# BeoModern_display.net
KiCad netlist of a schematic drawn in EAGLE
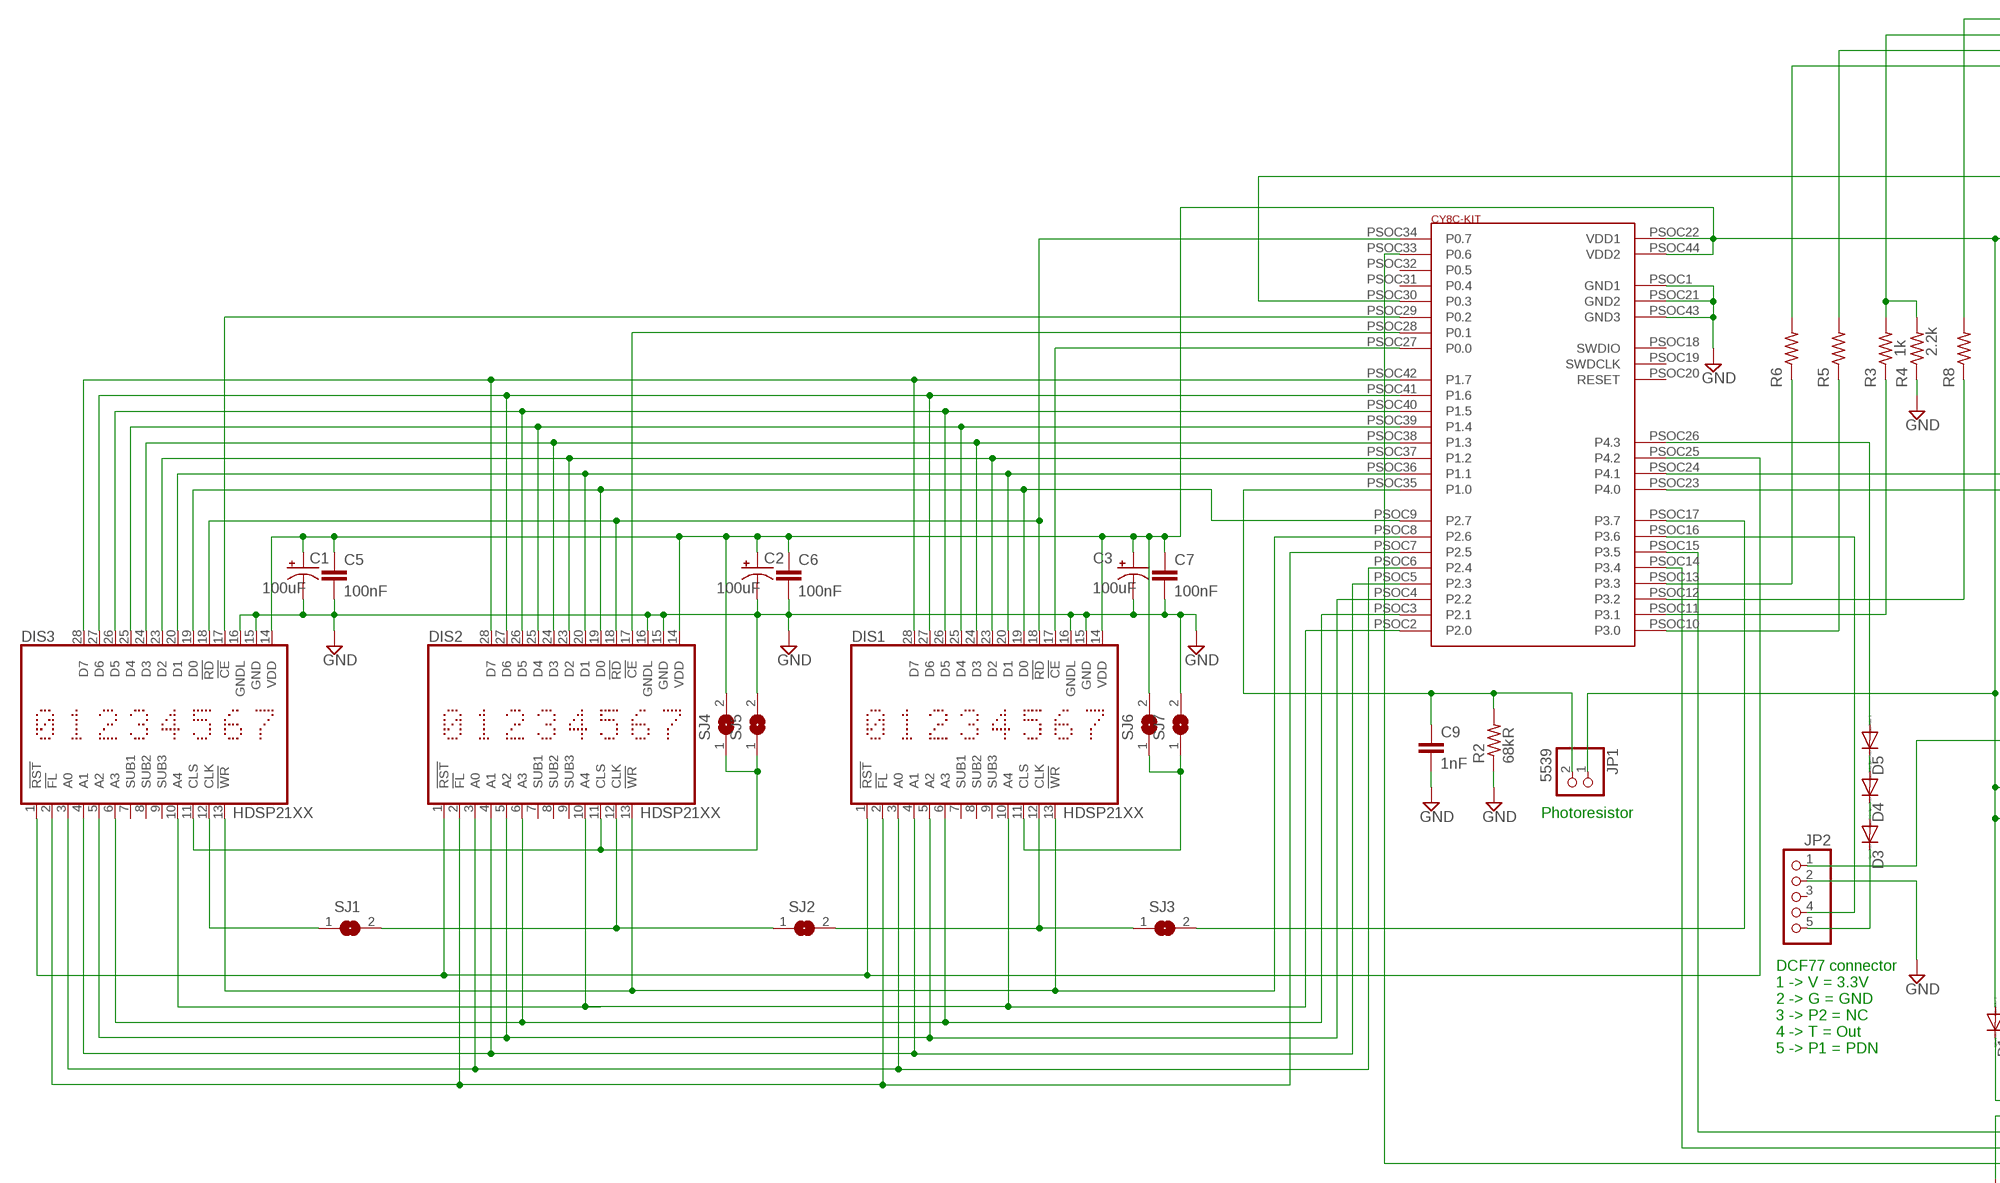
[diagram p0: schematic, sheet 1, part 1 of 2]
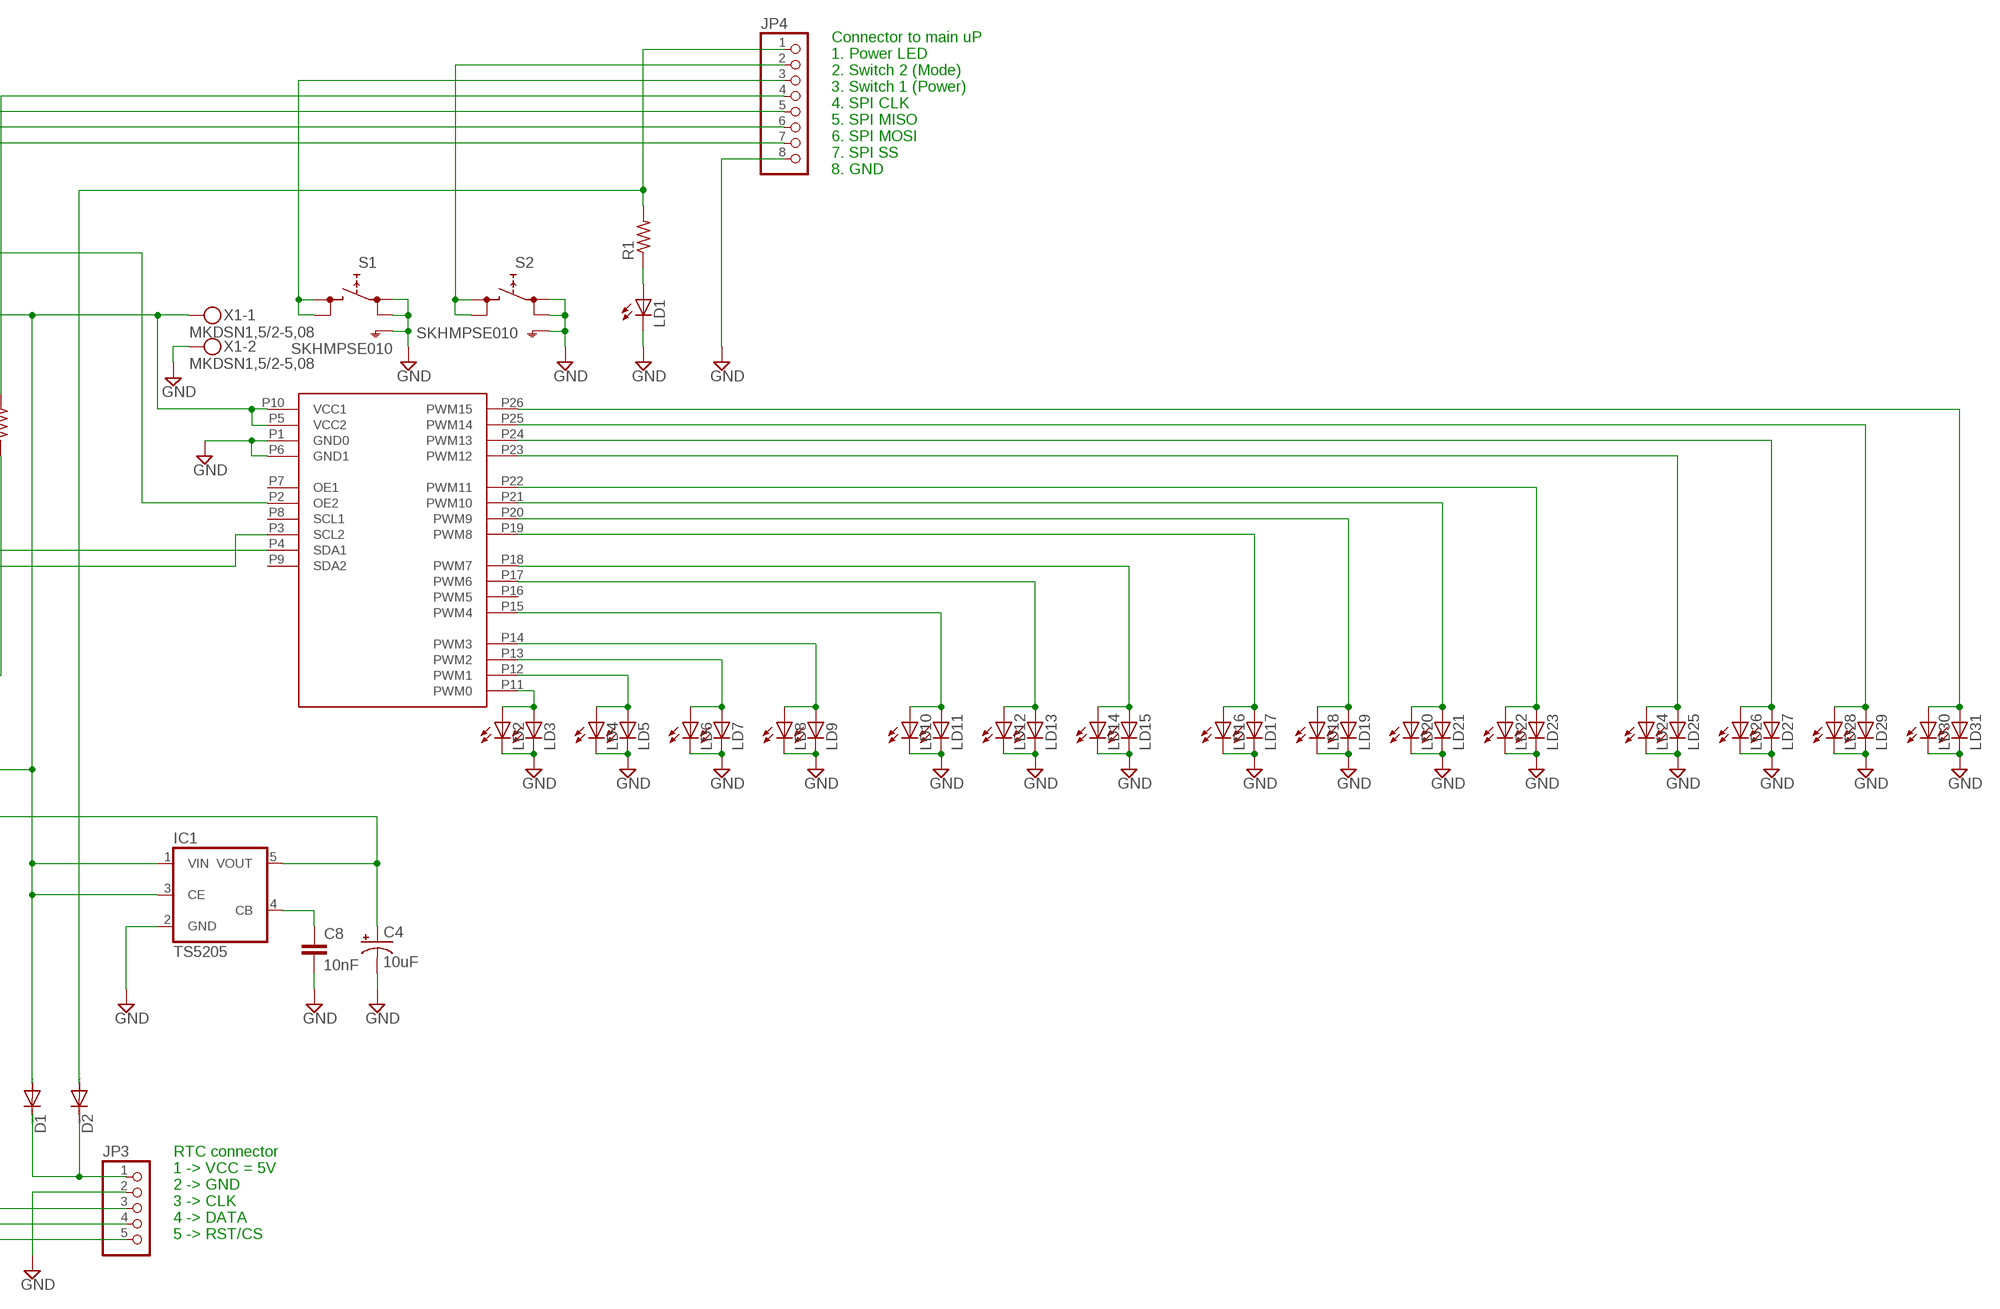
[diagram p1: schematic, sheet 1, part 2 of 2]

(export (version "E")
  (design (tool "Eeschema 10.0.6"))
  (components
    (comp (ref "C1")
      (value "100uF")
      (footprint "eagle-import:E15-5")
      (libsource (lib "eagle-import") (part "CPOL-USE15-5AXIAL"))
    )
    (comp (ref "C2")
      (value "100uF")
      (footprint "eagle-import:E15-5")
      (libsource (lib "eagle-import") (part "CPOL-USE15-5AXIAL"))
    )
    (comp (ref "C3")
      (value "100uF")
      (footprint "eagle-import:E15-5")
      (libsource (lib "eagle-import") (part "CPOL-USE15-5AXIAL"))
    )
    (comp (ref "C4")
      (value "10uF")
      (footprint "eagle-import:E2,5-5")
      (libsource (lib "eagle-import") (part "CPOL-USE2.5-5"))
    )
    (comp (ref "C5")
      (value "100nF")
      (footprint "eagle-import:C15B5")
      (libsource (lib "eagle-import") (part "C15/5"))
    )
    (comp (ref "C6")
      (value "100nF")
      (footprint "eagle-import:C15B5")
      (libsource (lib "eagle-import") (part "C15/5"))
    )
    (comp (ref "C7")
      (value "100nF")
      (footprint "eagle-import:C15B5")
      (libsource (lib "eagle-import") (part "C15/5"))
    )
    (comp (ref "C8")
      (value "10nF")
      (footprint "eagle-import:C2.5-2")
      (libsource (lib "eagle-import") (part "C2.5/2"))
    )
    (comp (ref "C9")
      (value "1nF")
      (footprint "eagle-import:C2.5-2")
      (libsource (lib "eagle-import") (part "C2.5/2"))
    )
    (comp (ref "D1")
      (value "DIODE-SOD80C")
      (footprint "eagle-import:SOD80C")
      (libsource (lib "eagle-import") (part "DIODE-SOD80C"))
    )
    (comp (ref "D2")
      (value "DIODE-SOD80C")
      (footprint "eagle-import:SOD80C")
      (libsource (lib "eagle-import") (part "DIODE-SOD80C"))
    )
    (comp (ref "D3")
      (value "DIODE-SOD80C")
      (footprint "eagle-import:SOD80C")
      (libsource (lib "eagle-import") (part "DIODE-SOD80C"))
    )
    (comp (ref "D4")
      (value "DIODE-SOD80C")
      (footprint "eagle-import:SOD80C")
      (libsource (lib "eagle-import") (part "DIODE-SOD80C"))
    )
    (comp (ref "D5")
      (value "DIODE-SOD80C")
      (footprint "eagle-import:SOD80C")
      (libsource (lib "eagle-import") (part "DIODE-SOD80C"))
    )
    (comp (ref "DIS1")
      (value "HDSP21XX")
      (footprint "eagle-import:HDSP21XX")
      (fields (field (name "MF") "AGILENT TECHNOLOGIES") (field (name "MPN") "HDSP-2179"))
      (libsource (lib "eagle-import") (part "HDSP21XX"))
    )
    (comp (ref "DIS2")
      (value "HDSP21XX")
      (footprint "eagle-import:HDSP21XX")
      (fields (field (name "MF") "AGILENT TECHNOLOGIES") (field (name "MPN") "HDSP-2179"))
      (libsource (lib "eagle-import") (part "HDSP21XX"))
    )
    (comp (ref "DIS3")
      (value "HDSP21XX")
      (footprint "eagle-import:HDSP21XX")
      (fields (field (name "MF") "AGILENT TECHNOLOGIES") (field (name "MPN") "HDSP-2179"))
      (libsource (lib "eagle-import") (part "HDSP21XX"))
    )
    (comp (ref "IC1")
      (value "TS5205")
      (footprint "eagle-import:SOT25")
      (libsource (lib "eagle-import") (part "TS5205"))
    )
    (comp (ref "JP1")
      (value "5539")
      (footprint "eagle-import:1X02")
      (libsource (lib "eagle-import") (part "PINHD-1X2"))
    )
    (comp (ref "JP2")
      (value "PINHD-1X5")
      (footprint "eagle-import:1X05")
      (libsource (lib "eagle-import") (part "PINHD-1X5"))
    )
    (comp (ref "JP3")
      (value "PINHD-1X5")
      (footprint "eagle-import:1X05")
      (libsource (lib "eagle-import") (part "PINHD-1X5"))
    )
    (comp (ref "JP4")
      (value "PINHD-1X8")
      (footprint "eagle-import:1X08")
      (libsource (lib "eagle-import") (part "PINHD-1X8"))
    )
    (comp (ref "LD1")
      (value "TLLR4400")
      (footprint "eagle-import:LED3MM")
      (fields (field (name "MF") "VISHAY SEMICONDUCTOR"))
      (libsource (lib "eagle-import") (part "TLLR4400"))
    )
    (comp (ref "LD2")
      (value "TLLR4400")
      (footprint "eagle-import:LED3MM")
      (fields (field (name "MF") "VISHAY SEMICONDUCTOR"))
      (libsource (lib "eagle-import") (part "TLLR4400"))
    )
    (comp (ref "LD3")
      (value "TLLR4400")
      (footprint "eagle-import:LED3MM")
      (fields (field (name "MF") "VISHAY SEMICONDUCTOR"))
      (libsource (lib "eagle-import") (part "TLLR4400"))
    )
    (comp (ref "LD4")
      (value "TLLR4400")
      (footprint "eagle-import:LED3MM")
      (fields (field (name "MF") "VISHAY SEMICONDUCTOR"))
      (libsource (lib "eagle-import") (part "TLLR4400"))
    )
    (comp (ref "LD5")
      (value "TLLR4400")
      (footprint "eagle-import:LED3MM")
      (fields (field (name "MF") "VISHAY SEMICONDUCTOR"))
      (libsource (lib "eagle-import") (part "TLLR4400"))
    )
    (comp (ref "LD6")
      (value "TLLR4400")
      (footprint "eagle-import:LED3MM")
      (fields (field (name "MF") "VISHAY SEMICONDUCTOR"))
      (libsource (lib "eagle-import") (part "TLLR4400"))
    )
    (comp (ref "LD7")
      (value "TLLR4400")
      (footprint "eagle-import:LED3MM")
      (fields (field (name "MF") "VISHAY SEMICONDUCTOR"))
      (libsource (lib "eagle-import") (part "TLLR4400"))
    )
    (comp (ref "LD8")
      (value "TLLR4400")
      (footprint "eagle-import:LED3MM")
      (fields (field (name "MF") "VISHAY SEMICONDUCTOR"))
      (libsource (lib "eagle-import") (part "TLLR4400"))
    )
    (comp (ref "LD9")
      (value "TLLR4400")
      (footprint "eagle-import:LED3MM")
      (fields (field (name "MF") "VISHAY SEMICONDUCTOR"))
      (libsource (lib "eagle-import") (part "TLLR4400"))
    )
    (comp (ref "LD10")
      (value "TLLR4400")
      (footprint "eagle-import:LED3MM")
      (fields (field (name "MF") "VISHAY SEMICONDUCTOR"))
      (libsource (lib "eagle-import") (part "TLLR4400"))
    )
    (comp (ref "LD11")
      (value "TLLR4400")
      (footprint "eagle-import:LED3MM")
      (fields (field (name "MF") "VISHAY SEMICONDUCTOR"))
      (libsource (lib "eagle-import") (part "TLLR4400"))
    )
    (comp (ref "LD12")
      (value "TLLR4400")
      (footprint "eagle-import:LED3MM")
      (fields (field (name "MF") "VISHAY SEMICONDUCTOR"))
      (libsource (lib "eagle-import") (part "TLLR4400"))
    )
    (comp (ref "LD13")
      (value "TLLR4400")
      (footprint "eagle-import:LED3MM")
      (fields (field (name "MF") "VISHAY SEMICONDUCTOR"))
      (libsource (lib "eagle-import") (part "TLLR4400"))
    )
    (comp (ref "LD14")
      (value "TLLR4400")
      (footprint "eagle-import:LED3MM")
      (fields (field (name "MF") "VISHAY SEMICONDUCTOR"))
      (libsource (lib "eagle-import") (part "TLLR4400"))
    )
    (comp (ref "LD15")
      (value "TLLR4400")
      (footprint "eagle-import:LED3MM")
      (fields (field (name "MF") "VISHAY SEMICONDUCTOR"))
      (libsource (lib "eagle-import") (part "TLLR4400"))
    )
    (comp (ref "LD16")
      (value "TLLR4400")
      (footprint "eagle-import:LED3MM")
      (fields (field (name "MF") "VISHAY SEMICONDUCTOR"))
      (libsource (lib "eagle-import") (part "TLLR4400"))
    )
    (comp (ref "LD17")
      (value "TLLR4400")
      (footprint "eagle-import:LED3MM")
      (fields (field (name "MF") "VISHAY SEMICONDUCTOR"))
      (libsource (lib "eagle-import") (part "TLLR4400"))
    )
    (comp (ref "LD18")
      (value "TLLR4400")
      (footprint "eagle-import:LED3MM")
      (fields (field (name "MF") "VISHAY SEMICONDUCTOR"))
      (libsource (lib "eagle-import") (part "TLLR4400"))
    )
    (comp (ref "LD19")
      (value "TLLR4400")
      (footprint "eagle-import:LED3MM")
      (fields (field (name "MF") "VISHAY SEMICONDUCTOR"))
      (libsource (lib "eagle-import") (part "TLLR4400"))
    )
    (comp (ref "LD20")
      (value "TLLR4400")
      (footprint "eagle-import:LED3MM")
      (fields (field (name "MF") "VISHAY SEMICONDUCTOR"))
      (libsource (lib "eagle-import") (part "TLLR4400"))
    )
    (comp (ref "LD21")
      (value "TLLR4400")
      (footprint "eagle-import:LED3MM")
      (fields (field (name "MF") "VISHAY SEMICONDUCTOR"))
      (libsource (lib "eagle-import") (part "TLLR4400"))
    )
    (comp (ref "LD22")
      (value "TLLR4400")
      (footprint "eagle-import:LED3MM")
      (fields (field (name "MF") "VISHAY SEMICONDUCTOR"))
      (libsource (lib "eagle-import") (part "TLLR4400"))
    )
    (comp (ref "LD23")
      (value "TLLR4400")
      (footprint "eagle-import:LED3MM")
      (fields (field (name "MF") "VISHAY SEMICONDUCTOR"))
      (libsource (lib "eagle-import") (part "TLLR4400"))
    )
    (comp (ref "LD24")
      (value "TLLR4400")
      (footprint "eagle-import:LED3MM")
      (fields (field (name "MF") "VISHAY SEMICONDUCTOR"))
      (libsource (lib "eagle-import") (part "TLLR4400"))
    )
    (comp (ref "LD25")
      (value "TLLR4400")
      (footprint "eagle-import:LED3MM")
      (fields (field (name "MF") "VISHAY SEMICONDUCTOR"))
      (libsource (lib "eagle-import") (part "TLLR4400"))
    )
    (comp (ref "LD26")
      (value "TLLR4400")
      (footprint "eagle-import:LED3MM")
      (fields (field (name "MF") "VISHAY SEMICONDUCTOR"))
      (libsource (lib "eagle-import") (part "TLLR4400"))
    )
    (comp (ref "LD27")
      (value "TLLR4400")
      (footprint "eagle-import:LED3MM")
      (fields (field (name "MF") "VISHAY SEMICONDUCTOR"))
      (libsource (lib "eagle-import") (part "TLLR4400"))
    )
    (comp (ref "LD28")
      (value "TLLR4400")
      (footprint "eagle-import:LED3MM")
      (fields (field (name "MF") "VISHAY SEMICONDUCTOR"))
      (libsource (lib "eagle-import") (part "TLLR4400"))
    )
    (comp (ref "LD29")
      (value "TLLR4400")
      (footprint "eagle-import:LED3MM")
      (fields (field (name "MF") "VISHAY SEMICONDUCTOR"))
      (libsource (lib "eagle-import") (part "TLLR4400"))
    )
    (comp (ref "LD30")
      (value "TLLR4400")
      (footprint "eagle-import:LED3MM")
      (fields (field (name "MF") "VISHAY SEMICONDUCTOR"))
      (libsource (lib "eagle-import") (part "TLLR4400"))
    )
    (comp (ref "LD31")
      (value "TLLR4400")
      (footprint "eagle-import:LED3MM")
      (fields (field (name "MF") "VISHAY SEMICONDUCTOR"))
      (libsource (lib "eagle-import") (part "TLLR4400"))
    )
    (comp (ref "R1")
      (value "R-US_0207/10")
      (footprint "eagle-import:0207_10")
      (libsource (lib "eagle-import") (part "R-US_0207/10"))
    )
    (comp (ref "R2")
      (value "68kR")
      (footprint "eagle-import:0207_10")
      (libsource (lib "eagle-import") (part "R-US_0207/10"))
    )
    (comp (ref "R3")
      (value "1k")
      (footprint "eagle-import:0207_10")
      (libsource (lib "eagle-import") (part "R-US_0207/10"))
    )
    (comp (ref "R4")
      (value "2.2k")
      (footprint "eagle-import:0207_10")
      (libsource (lib "eagle-import") (part "R-US_0207/10"))
    )
    (comp (ref "R5")
      (value "R-US_0207/10")
      (footprint "eagle-import:0207_10")
      (libsource (lib "eagle-import") (part "R-US_0207/10"))
    )
    (comp (ref "R6")
      (value "R-US_0207/10")
      (footprint "eagle-import:0207_10")
      (libsource (lib "eagle-import") (part "R-US_0207/10"))
    )
    (comp (ref "R8")
      (value "R-US_0207/10")
      (footprint "eagle-import:0207_10")
      (libsource (lib "eagle-import") (part "R-US_0207/10"))
    )
    (comp (ref "S1")
      (value "SKHMPSE010")
      (footprint "eagle-import:SKHMPXE010")
      (libsource (lib "eagle-import") (part "SKHMPE010S"))
    )
    (comp (ref "S2")
      (value "SKHMPSE010")
      (footprint "eagle-import:SKHMPXE010")
      (libsource (lib "eagle-import") (part "SKHMPE010S"))
    )
    (comp (ref "SJ1") (value "SJ") (footprint "eagle-import:SJ") (libsource (lib "eagle-import") (part "SJ")))
    (comp (ref "SJ2") (value "SJ") (footprint "eagle-import:SJ") (libsource (lib "eagle-import") (part "SJ")))
    (comp (ref "SJ3") (value "SJ") (footprint "eagle-import:SJ") (libsource (lib "eagle-import") (part "SJ")))
    (comp (ref "SJ4") (value "SJ") (footprint "eagle-import:SJ") (libsource (lib "eagle-import") (part "SJ")))
    (comp (ref "SJ5") (value "SJ") (footprint "eagle-import:SJ") (libsource (lib "eagle-import") (part "SJ")))
    (comp (ref "SJ6") (value "SJ") (footprint "eagle-import:SJ") (libsource (lib "eagle-import") (part "SJ")))
    (comp (ref "SJ7") (value "SJ") (footprint "eagle-import:SJ") (libsource (lib "eagle-import") (part "SJ")))
    (comp (ref "U$9")
      (value "CY8C-KIT")
      (footprint "eagle-import:CY8C-KIT-FOOTPRINT")
      (libsource (lib "eagle-import") (part "CY8C-KIT"))
    )
    (comp (ref "U$10")
      (value "PCA9685")
      (footprint "eagle-import:PCA9685_FOOTPRINT")
      (libsource (lib "eagle-import") (part "PCA9685"))
    )
    (comp (ref "X1")
      (value "MKDSN1,5/2-5,08")
      (footprint "eagle-import:MKDSN1,5_2-5,08")
      (libsource (lib "eagle-import") (part "MKDSN1,5/2-5,08"))
    )
  )
  (nets
    (net (code "1") (name "GND") (class "Default")
      (node (ref "C1") (pin "-") (pinfunction "-_-") (pintype "passive"))
      (node (ref "C2") (pin "-") (pinfunction "-_-") (pintype "passive"))
      (node (ref "C3") (pin "-") (pinfunction "-_-") (pintype "passive"))
      (node (ref "C4") (pin "-") (pinfunction "-_-") (pintype "passive"))
      (node (ref "C5") (pin "2") (pinfunction "2_2") (pintype "passive"))
      (node (ref "C6") (pin "2") (pinfunction "2_2") (pintype "passive"))
      (node (ref "C7") (pin "2") (pinfunction "2_2") (pintype "passive"))
      (node (ref "C8") (pin "2") (pinfunction "2_2") (pintype "passive"))
      (node (ref "C9") (pin "2") (pinfunction "2_2") (pintype "passive"))
      (node (ref "DIS1") (pin "15") (pinfunction "GND_15") (pintype "power_in"))
      (node (ref "DIS1") (pin "16") (pinfunction "GNDL_16") (pintype "power_in"))
      (node (ref "DIS2") (pin "15") (pinfunction "GND_15") (pintype "power_in"))
      (node (ref "DIS2") (pin "16") (pinfunction "GNDL_16") (pintype "power_in"))
      (node (ref "DIS3") (pin "15") (pinfunction "GND_15") (pintype "power_in"))
      (node (ref "DIS3") (pin "16") (pinfunction "GNDL_16") (pintype "power_in"))
      (node (ref "IC1") (pin "2") (pinfunction "GND_2") (pintype "passive"))
      (node (ref "JP2") (pin "2") (pinfunction "2_2") (pintype "passive"))
      (node (ref "JP3") (pin "2") (pinfunction "2_2") (pintype "passive"))
      (node (ref "JP4") (pin "8") (pinfunction "8_8") (pintype "passive"))
      (node (ref "LD1") (pin "K") (pinfunction "C_K") (pintype "passive"))
      (node (ref "LD10") (pin "K") (pinfunction "C_K") (pintype "passive"))
      (node (ref "LD11") (pin "K") (pinfunction "C_K") (pintype "passive"))
      (node (ref "LD12") (pin "K") (pinfunction "C_K") (pintype "passive"))
      (node (ref "LD13") (pin "K") (pinfunction "C_K") (pintype "passive"))
      (node (ref "LD14") (pin "K") (pinfunction "C_K") (pintype "passive"))
      (node (ref "LD15") (pin "K") (pinfunction "C_K") (pintype "passive"))
      (node (ref "LD16") (pin "K") (pinfunction "C_K") (pintype "passive"))
      (node (ref "LD17") (pin "K") (pinfunction "C_K") (pintype "passive"))
      (node (ref "LD18") (pin "K") (pinfunction "C_K") (pintype "passive"))
      (node (ref "LD19") (pin "K") (pinfunction "C_K") (pintype "passive"))
      (node (ref "LD2") (pin "K") (pinfunction "C_K") (pintype "passive"))
      (node (ref "LD20") (pin "K") (pinfunction "C_K") (pintype "passive"))
      (node (ref "LD21") (pin "K") (pinfunction "C_K") (pintype "passive"))
      (node (ref "LD22") (pin "K") (pinfunction "C_K") (pintype "passive"))
      (node (ref "LD23") (pin "K") (pinfunction "C_K") (pintype "passive"))
      (node (ref "LD24") (pin "K") (pinfunction "C_K") (pintype "passive"))
      (node (ref "LD25") (pin "K") (pinfunction "C_K") (pintype "passive"))
      (node (ref "LD26") (pin "K") (pinfunction "C_K") (pintype "passive"))
      (node (ref "LD27") (pin "K") (pinfunction "C_K") (pintype "passive"))
      (node (ref "LD28") (pin "K") (pinfunction "C_K") (pintype "passive"))
      (node (ref "LD29") (pin "K") (pinfunction "C_K") (pintype "passive"))
      (node (ref "LD3") (pin "K") (pinfunction "C_K") (pintype "passive"))
      (node (ref "LD30") (pin "K") (pinfunction "C_K") (pintype "passive"))
      (node (ref "LD31") (pin "K") (pinfunction "C_K") (pintype "passive"))
      (node (ref "LD4") (pin "K") (pinfunction "C_K") (pintype "passive"))
      (node (ref "LD5") (pin "K") (pinfunction "C_K") (pintype "passive"))
      (node (ref "LD6") (pin "K") (pinfunction "C_K") (pintype "passive"))
      (node (ref "LD7") (pin "K") (pinfunction "C_K") (pintype "passive"))
      (node (ref "LD8") (pin "K") (pinfunction "C_K") (pintype "passive"))
      (node (ref "LD9") (pin "K") (pinfunction "C_K") (pintype "passive"))
      (node (ref "R2") (pin "1") (pinfunction "1_1") (pintype "passive"))
      (node (ref "R4") (pin "1") (pinfunction "1_1") (pintype "passive"))
      (node (ref "S1") (pin "1") (pinfunction "1.1_1") (pintype "passive"))
      (node (ref "S1") (pin "2") (pinfunction "1.2_2") (pintype "passive"))
      (node (ref "S1") (pin "5") (pinfunction "SH_5") (pintype "passive"))
      (node (ref "S2") (pin "1") (pinfunction "1.1_1") (pintype "passive"))
      (node (ref "S2") (pin "2") (pinfunction "1.2_2") (pintype "passive"))
      (node (ref "S2") (pin "5") (pinfunction "SH_5") (pintype "passive"))
      (node (ref "SJ5") (pin "2") (pinfunction "2_2") (pintype "passive"))
      (node (ref "SJ7") (pin "2") (pinfunction "2_2") (pintype "passive"))
      (node (ref "U$10") (pin "P1") (pinfunction "GND0_P1") (pintype "bidirectional"))
      (node (ref "U$10") (pin "P6") (pinfunction "GND1_P6") (pintype "bidirectional"))
      (node (ref "U$9") (pin "PSOC1") (pinfunction "GND1_PSOC1") (pintype "bidirectional"))
      (node (ref "U$9") (pin "PSOC21") (pinfunction "GND2_PSOC21") (pintype "bidirectional"))
      (node (ref "U$9") (pin "PSOC43") (pinfunction "GND3_PSOC43") (pintype "bidirectional"))
      (node (ref "X1") (pin "2") (pinfunction "KL_2") (pintype "passive"))
    )
    (net (code "2") (name "Net-(D1-PadC)") (class "Default")
      (node (ref "D1") (pin "C") (pinfunction "C_C") (pintype "passive"))
      (node (ref "D2") (pin "C") (pinfunction "C_C") (pintype "passive"))
      (node (ref "JP3") (pin "1") (pinfunction "1_1") (pintype "passive"))
    )
    (net (code "3") (name "Net-(D2-PadA)") (class "Default")
      (node (ref "D2") (pin "A") (pinfunction "A_A") (pintype "passive"))
      (node (ref "JP4") (pin "1") (pinfunction "1_1") (pintype "passive"))
      (node (ref "R1") (pin "2") (pinfunction "2_2") (pintype "passive"))
    )
    (net (code "4") (name "Net-(D3-PadA)") (class "Default")
      (node (ref "D3") (pin "A") (pinfunction "A_A") (pintype "passive"))
      (node (ref "D4") (pin "C") (pinfunction "C_C") (pintype "passive"))
    )
    (net (code "5") (name "Net-(D3-PadC)") (class "Default")
      (node (ref "D3") (pin "C") (pinfunction "C_C") (pintype "passive"))
      (node (ref "JP2") (pin "5") (pinfunction "5_5") (pintype "passive"))
    )
    (net (code "6") (name "Net-(D4-PadA)") (class "Default")
      (node (ref "D4") (pin "A") (pinfunction "A_A") (pintype "passive"))
      (node (ref "D5") (pin "C") (pinfunction "C_C") (pintype "passive"))
    )
    (net (code "7") (name "Net-(DIS1-A0)") (class "Default")
      (node (ref "DIS1") (pin "3") (pinfunction "A0_3") (pintype "input"))
      (node (ref "DIS2") (pin "3") (pinfunction "A0_3") (pintype "input"))
      (node (ref "DIS3") (pin "3") (pinfunction "A0_3") (pintype "input"))
      (node (ref "U$9") (pin "PSOC6") (pinfunction "P2.4_PSOC6") (pintype "bidirectional"))
    )
    (net (code "8") (name "Net-(DIS1-A1)") (class "Default")
      (node (ref "DIS1") (pin "4") (pinfunction "A1_4") (pintype "input"))
      (node (ref "DIS2") (pin "4") (pinfunction "A1_4") (pintype "input"))
      (node (ref "DIS3") (pin "4") (pinfunction "A1_4") (pintype "input"))
      (node (ref "U$9") (pin "PSOC5") (pinfunction "P2.3_PSOC5") (pintype "bidirectional"))
    )
    (net (code "9") (name "Net-(DIS1-A2)") (class "Default")
      (node (ref "DIS1") (pin "5") (pinfunction "A2_5") (pintype "input"))
      (node (ref "DIS2") (pin "5") (pinfunction "A2_5") (pintype "input"))
      (node (ref "DIS3") (pin "5") (pinfunction "A2_5") (pintype "input"))
      (node (ref "U$9") (pin "PSOC4") (pinfunction "P2.2_PSOC4") (pintype "bidirectional"))
    )
    (net (code "10") (name "Net-(DIS1-A3)") (class "Default")
      (node (ref "DIS1") (pin "6") (pinfunction "A3_6") (pintype "input"))
      (node (ref "DIS2") (pin "6") (pinfunction "A3_6") (pintype "input"))
      (node (ref "DIS3") (pin "6") (pinfunction "A3_6") (pintype "input"))
      (node (ref "U$9") (pin "PSOC3") (pinfunction "P2.1_PSOC3") (pintype "bidirectional"))
    )
    (net (code "11") (name "Net-(DIS1-A4)") (class "Default")
      (node (ref "DIS1") (pin "10") (pinfunction "A4_10") (pintype "input"))
      (node (ref "DIS2") (pin "10") (pinfunction "A4_10") (pintype "input"))
      (node (ref "DIS3") (pin "10") (pinfunction "A4_10") (pintype "input"))
      (node (ref "U$9") (pin "PSOC2") (pinfunction "P2.0_PSOC2") (pintype "bidirectional"))
    )
    (net (code "12") (name "Net-(DIS1-CLK)") (class "Default")
      (node (ref "DIS1") (pin "12") (pinfunction "CLK_12") (pintype "input"))
      (node (ref "SJ2") (pin "2") (pinfunction "2_2") (pintype "passive"))
      (node (ref "SJ3") (pin "1") (pinfunction "1_1") (pintype "passive"))
    )
    (net (code "13") (name "Net-(DIS1-CLS)") (class "Default")
      (node (ref "DIS1") (pin "11") (pinfunction "CLS_11") (pintype "input"))
      (node (ref "SJ6") (pin "1") (pinfunction "1_1") (pintype "passive"))
      (node (ref "SJ7") (pin "1") (pinfunction "1_1") (pintype "passive"))
    )
    (net (code "14") (name "Net-(DIS1-D0)") (class "Default")
      (node (ref "DIS1") (pin "19") (pinfunction "D0_19") (pintype "input"))
      (node (ref "DIS2") (pin "19") (pinfunction "D0_19") (pintype "input"))
      (node (ref "DIS3") (pin "19") (pinfunction "D0_19") (pintype "input"))
      (node (ref "U$9") (pin "PSOC9") (pinfunction "P2.7_PSOC9") (pintype "bidirectional"))
    )
    (net (code "15") (name "Net-(DIS1-D1)") (class "Default")
      (node (ref "DIS1") (pin "20") (pinfunction "D1_20") (pintype "input"))
      (node (ref "DIS2") (pin "20") (pinfunction "D1_20") (pintype "input"))
      (node (ref "DIS3") (pin "20") (pinfunction "D1_20") (pintype "input"))
      (node (ref "U$9") (pin "PSOC36") (pinfunction "P1.1_PSOC36") (pintype "bidirectional"))
    )
    (net (code "16") (name "Net-(DIS1-D2)") (class "Default")
      (node (ref "DIS1") (pin "23") (pinfunction "D2_23") (pintype "input"))
      (node (ref "DIS2") (pin "23") (pinfunction "D2_23") (pintype "input"))
      (node (ref "DIS3") (pin "23") (pinfunction "D2_23") (pintype "input"))
      (node (ref "U$9") (pin "PSOC37") (pinfunction "P1.2_PSOC37") (pintype "bidirectional"))
    )
    (net (code "17") (name "Net-(DIS1-D3)") (class "Default")
      (node (ref "DIS1") (pin "24") (pinfunction "D3_24") (pintype "input"))
      (node (ref "DIS2") (pin "24") (pinfunction "D3_24") (pintype "input"))
      (node (ref "DIS3") (pin "24") (pinfunction "D3_24") (pintype "input"))
      (node (ref "U$9") (pin "PSOC38") (pinfunction "P1.3_PSOC38") (pintype "bidirectional"))
    )
    (net (code "18") (name "Net-(DIS1-D4)") (class "Default")
      (node (ref "DIS1") (pin "25") (pinfunction "D4_25") (pintype "input"))
      (node (ref "DIS2") (pin "25") (pinfunction "D4_25") (pintype "input"))
      (node (ref "DIS3") (pin "25") (pinfunction "D4_25") (pintype "input"))
      (node (ref "U$9") (pin "PSOC39") (pinfunction "P1.4_PSOC39") (pintype "bidirectional"))
    )
    (net (code "19") (name "Net-(DIS1-D5)") (class "Default")
      (node (ref "DIS1") (pin "26") (pinfunction "D5_26") (pintype "input"))
      (node (ref "DIS2") (pin "26") (pinfunction "D5_26") (pintype "input"))
      (node (ref "DIS3") (pin "26") (pinfunction "D5_26") (pintype "input"))
      (node (ref "U$9") (pin "PSOC40") (pinfunction "P1.5_PSOC40") (pintype "bidirectional"))
    )
    (net (code "20") (name "Net-(DIS1-D6)") (class "Default")
      (node (ref "DIS1") (pin "27") (pinfunction "D6_27") (pintype "input"))
      (node (ref "DIS2") (pin "27") (pinfunction "D6_27") (pintype "input"))
      (node (ref "DIS3") (pin "27") (pinfunction "D6_27") (pintype "input"))
      (node (ref "U$9") (pin "PSOC41") (pinfunction "P1.6_PSOC41") (pintype "bidirectional"))
    )
    (net (code "21") (name "Net-(DIS1-D7)") (class "Default")
      (node (ref "DIS1") (pin "28") (pinfunction "D7_28") (pintype "input"))
      (node (ref "DIS2") (pin "28") (pinfunction "D7_28") (pintype "input"))
      (node (ref "DIS3") (pin "28") (pinfunction "D7_28") (pintype "input"))
      (node (ref "U$9") (pin "PSOC42") (pinfunction "P1.7_PSOC42") (pintype "bidirectional"))
    )
    (net (code "22") (name "Net-(DIS1-VDD)") (class "Default")
      (node (ref "C1") (pin "+") (pinfunction "+_+") (pintype "passive"))
      (node (ref "C2") (pin "+") (pinfunction "+_+") (pintype "passive"))
      (node (ref "C3") (pin "+") (pinfunction "+_+") (pintype "passive"))
      (node (ref "C5") (pin "1") (pinfunction "1_1") (pintype "passive"))
      (node (ref "C6") (pin "1") (pinfunction "1_1") (pintype "passive"))
      (node (ref "C7") (pin "1") (pinfunction "1_1") (pintype "passive"))
      (node (ref "D1") (pin "A") (pinfunction "A_A") (pintype "passive"))
      (node (ref "DIS1") (pin "14") (pinfunction "VDD_14") (pintype "power_in"))
      (node (ref "DIS2") (pin "14") (pinfunction "VDD_14") (pintype "power_in"))
      (node (ref "DIS3") (pin "14") (pinfunction "VDD_14") (pintype "power_in"))
      (node (ref "IC1") (pin "1") (pinfunction "VIN_1") (pintype "input"))
      (node (ref "IC1") (pin "3") (pinfunction "CE_3") (pintype "input"))
      (node (ref "JP1") (pin "1") (pinfunction "1_1") (pintype "passive"))
      (node (ref "SJ4") (pin "2") (pinfunction "2_2") (pintype "passive"))
      (node (ref "SJ6") (pin "2") (pinfunction "2_2") (pintype "passive"))
      (node (ref "U$10") (pin "P10") (pinfunction "VCC1_P10") (pintype "bidirectional"))
      (node (ref "U$10") (pin "P5") (pinfunction "VCC2_P5") (pintype "bidirectional"))
      (node (ref "U$9") (pin "PSOC22") (pinfunction "VDD1_PSOC22") (pintype "bidirectional"))
      (node (ref "U$9") (pin "PSOC44") (pinfunction "VDD2_PSOC44") (pintype "bidirectional"))
      (node (ref "X1") (pin "1") (pinfunction "KL_1") (pintype "passive"))
    )
    (net (code "23") (name "Net-(DIS1-~{CE})") (class "Default")
      (node (ref "DIS1") (pin "17") (pinfunction "~{CE}_17") (pintype "input"))
      (node (ref "U$9") (pin "PSOC27") (pinfunction "P0.0_PSOC27") (pintype "bidirectional"))
    )
    (net (code "24") (name "Net-(DIS1-~{FL})") (class "Default")
      (node (ref "DIS1") (pin "2") (pinfunction "~{FL}_2") (pintype "input"))
      (node (ref "DIS2") (pin "2") (pinfunction "~{FL}_2") (pintype "input"))
      (node (ref "DIS3") (pin "2") (pinfunction "~{FL}_2") (pintype "input"))
      (node (ref "U$9") (pin "PSOC7") (pinfunction "P2.5_PSOC7") (pintype "bidirectional"))
    )
    (net (code "25") (name "Net-(DIS1-~{RD})") (class "Default")
      (node (ref "DIS1") (pin "18") (pinfunction "~{RD}_18") (pintype "input"))
      (node (ref "DIS2") (pin "18") (pinfunction "~{RD}_18") (pintype "input"))
      (node (ref "DIS3") (pin "18") (pinfunction "~{RD}_18") (pintype "input"))
      (node (ref "U$9") (pin "PSOC34") (pinfunction "P0.7_PSOC34") (pintype "bidirectional"))
    )
    (net (code "26") (name "Net-(DIS1-~{RST})") (class "Default")
      (node (ref "DIS1") (pin "1") (pinfunction "~{RST}_1") (pintype "input"))
      (node (ref "DIS2") (pin "1") (pinfunction "~{RST}_1") (pintype "input"))
      (node (ref "DIS3") (pin "1") (pinfunction "~{RST}_1") (pintype "input"))
      (node (ref "U$9") (pin "PSOC25") (pinfunction "P4.2_PSOC25") (pintype "bidirectional"))
    )
    (net (code "27") (name "Net-(DIS1-~{WR})") (class "Default")
      (node (ref "DIS1") (pin "13") (pinfunction "~{WR}_13") (pintype "input"))
      (node (ref "DIS2") (pin "13") (pinfunction "~{WR}_13") (pintype "input"))
      (node (ref "DIS3") (pin "13") (pinfunction "~{WR}_13") (pintype "input"))
      (node (ref "U$9") (pin "PSOC8") (pinfunction "P2.6_PSOC8") (pintype "bidirectional"))
    )
    (net (code "28") (name "Net-(DIS2-CLK)") (class "Default")
      (node (ref "DIS2") (pin "12") (pinfunction "CLK_12") (pintype "input"))
      (node (ref "SJ1") (pin "2") (pinfunction "2_2") (pintype "passive"))
      (node (ref "SJ2") (pin "1") (pinfunction "1_1") (pintype "passive"))
    )
    (net (code "29") (name "Net-(DIS2-CLS)") (class "Default")
      (node (ref "DIS2") (pin "11") (pinfunction "CLS_11") (pintype "input"))
      (node (ref "DIS3") (pin "11") (pinfunction "CLS_11") (pintype "input"))
      (node (ref "SJ4") (pin "1") (pinfunction "1_1") (pintype "passive"))
      (node (ref "SJ5") (pin "1") (pinfunction "1_1") (pintype "passive"))
    )
    (net (code "30") (name "Net-(DIS2-~{CE})") (class "Default")
      (node (ref "DIS2") (pin "17") (pinfunction "~{CE}_17") (pintype "input"))
      (node (ref "U$9") (pin "PSOC28") (pinfunction "P0.1_PSOC28") (pintype "bidirectional"))
    )
    (net (code "31") (name "Net-(DIS3-CLK)") (class "Default")
      (node (ref "DIS3") (pin "12") (pinfunction "CLK_12") (pintype "input"))
      (node (ref "SJ1") (pin "1") (pinfunction "1_1") (pintype "passive"))
    )
    (net (code "32") (name "Net-(DIS3-~{CE})") (class "Default")
      (node (ref "DIS3") (pin "17") (pinfunction "~{CE}_17") (pintype "input"))
      (node (ref "U$9") (pin "PSOC29") (pinfunction "P0.2_PSOC29") (pintype "bidirectional"))
    )
    (net (code "33") (name "Net-(IC1-CB)") (class "Default")
      (node (ref "C8") (pin "1") (pinfunction "1_1") (pintype "passive"))
      (node (ref "IC1") (pin "4") (pinfunction "CB_4") (pintype "input"))
    )
    (net (code "34") (name "Net-(IC1-VOUT)") (class "Default")
      (node (ref "C4") (pin "+") (pinfunction "+_+") (pintype "passive"))
      (node (ref "IC1") (pin "5") (pinfunction "VOUT_5") (pintype "passive"))
      (node (ref "JP2") (pin "1") (pinfunction "1_1") (pintype "passive"))
    )
    (net (code "35") (name "Net-(JP4-Pad4)") (class "Default")
      (node (ref "JP4") (pin "4") (pinfunction "4_4") (pintype "passive"))
      (node (ref "R8") (pin "2") (pinfunction "2_2") (pintype "passive"))
    )
    (net (code "36") (name "Net-(JP4-Pad5)") (class "Default")
      (node (ref "JP4") (pin "5") (pinfunction "5_5") (pintype "passive"))
      (node (ref "R3") (pin "2") (pinfunction "2_2") (pintype "passive"))
      (node (ref "R4") (pin "2") (pinfunction "2_2") (pintype "passive"))
    )
    (net (code "37") (name "Net-(JP4-Pad6)") (class "Default")
      (node (ref "JP4") (pin "6") (pinfunction "6_6") (pintype "passive"))
      (node (ref "R5") (pin "2") (pinfunction "2_2") (pintype "passive"))
    )
    (net (code "38") (name "Net-(JP4-Pad7)") (class "Default")
      (node (ref "JP4") (pin "7") (pinfunction "7_7") (pintype "passive"))
      (node (ref "R6") (pin "2") (pinfunction "2_2") (pintype "passive"))
    )
    (net (code "39") (name "Net-(LD1-PadA)") (class "Default")
      (node (ref "LD1") (pin "A") (pinfunction "A_A") (pintype "passive"))
      (node (ref "R1") (pin "1") (pinfunction "1_1") (pintype "passive"))
    )
    (net (code "40") (name "Net-(S1-2.1)") (class "Default")
      (node (ref "JP4") (pin "3") (pinfunction "3_3") (pintype "passive"))
      (node (ref "S1") (pin "3") (pinfunction "2.1_3") (pintype "passive"))
      (node (ref "S1") (pin "4") (pinfunction "2.2_4") (pintype "passive"))
    )
    (net (code "41") (name "Net-(S2-2.1)") (class "Default")
      (node (ref "JP4") (pin "2") (pinfunction "2_2") (pintype "passive"))
      (node (ref "S2") (pin "3") (pinfunction "2.1_3") (pintype "passive"))
      (node (ref "S2") (pin "4") (pinfunction "2.2_4") (pintype "passive"))
    )
    (net (code "42") (name "Net-(U$9-P0.6)") (class "Default")
      (node (ref "JP3") (pin "5") (pinfunction "5_5") (pintype "passive"))
      (node (ref "U$9") (pin "PSOC33") (pinfunction "P0.6_PSOC33") (pintype "bidirectional"))
    )
    (net (code "43") (name "Net-(U$9-P1.0)") (class "Default")
      (node (ref "C9") (pin "1") (pinfunction "1_1") (pintype "passive"))
      (node (ref "JP1") (pin "2") (pinfunction "2_2") (pintype "passive"))
      (node (ref "R2") (pin "2") (pinfunction "2_2") (pintype "passive"))
      (node (ref "U$9") (pin "PSOC35") (pinfunction "P1.0_PSOC35") (pintype "bidirectional"))
    )
    (net (code "44") (name "Net-(U$9-P3.0)") (class "Default")
      (node (ref "R5") (pin "1") (pinfunction "1_1") (pintype "passive"))
      (node (ref "U$9") (pin "PSOC10") (pinfunction "P3.0_PSOC10") (pintype "bidirectional"))
    )
    (net (code "45") (name "Net-(U$9-P3.1)") (class "Default")
      (node (ref "R3") (pin "1") (pinfunction "1_1") (pintype "passive"))
      (node (ref "U$9") (pin "PSOC11") (pinfunction "P3.1_PSOC11") (pintype "bidirectional"))
    )
    (net (code "46") (name "Net-(U$9-P3.2)") (class "Default")
      (node (ref "R8") (pin "1") (pinfunction "1_1") (pintype "passive"))
      (node (ref "U$9") (pin "PSOC12") (pinfunction "P3.2_PSOC12") (pintype "bidirectional"))
    )
    (net (code "47") (name "Net-(U$9-P3.3)") (class "Default")
      (node (ref "R6") (pin "1") (pinfunction "1_1") (pintype "passive"))
      (node (ref "U$9") (pin "PSOC13") (pinfunction "P3.3_PSOC13") (pintype "bidirectional"))
    )
    (net (code "48") (name "Net-(U$9-P3.4)") (class "Default")
      (node (ref "JP3") (pin "4") (pinfunction "4_4") (pintype "passive"))
      (node (ref "U$9") (pin "PSOC14") (pinfunction "P3.4_PSOC14") (pintype "bidirectional"))
    )
    (net (code "49") (name "Net-(U$9-P3.5)") (class "Default")
      (node (ref "JP3") (pin "3") (pinfunction "3_3") (pintype "passive"))
      (node (ref "U$9") (pin "PSOC15") (pinfunction "P3.5_PSOC15") (pintype "bidirectional"))
    )
    (net (code "50") (name "Net-(U$9-P3.6)") (class "Default")
      (node (ref "JP2") (pin "4") (pinfunction "4_4") (pintype "passive"))
      (node (ref "U$9") (pin "PSOC16") (pinfunction "P3.6_PSOC16") (pintype "bidirectional"))
    )
    (net (code "51") (name "Net-(U$9-P3.7)") (class "Default")
      (node (ref "SJ3") (pin "2") (pinfunction "2_2") (pintype "passive"))
      (node (ref "U$9") (pin "PSOC17") (pinfunction "P3.7_PSOC17") (pintype "bidirectional"))
    )
    (net (code "52") (name "Net-(U$9-P4.3)") (class "Default")
      (node (ref "D5") (pin "A") (pinfunction "A_A") (pintype "passive"))
      (node (ref "U$9") (pin "PSOC26") (pinfunction "P4.3_PSOC26") (pintype "bidirectional"))
    )
    (net (code "53") (name "Net-(U$10-OE2)") (class "Default")
      (node (ref "U$10") (pin "P2") (pinfunction "OE2_P2") (pintype "bidirectional"))
      (node (ref "U$9") (pin "PSOC30") (pinfunction "P0.3_PSOC30") (pintype "bidirectional"))
    )
    (net (code "54") (name "Net-(U$10-PWM0)") (class "Default")
      (node (ref "LD2") (pin "A") (pinfunction "A_A") (pintype "passive"))
      (node (ref "LD3") (pin "A") (pinfunction "A_A") (pintype "passive"))
      (node (ref "U$10") (pin "P11") (pinfunction "PWM0_P11") (pintype "bidirectional"))
    )
    (net (code "55") (name "Net-(U$10-PWM1)") (class "Default")
      (node (ref "LD4") (pin "A") (pinfunction "A_A") (pintype "passive"))
      (node (ref "LD5") (pin "A") (pinfunction "A_A") (pintype "passive"))
      (node (ref "U$10") (pin "P12") (pinfunction "PWM1_P12") (pintype "bidirectional"))
    )
    (net (code "56") (name "Net-(U$10-PWM2)") (class "Default")
      (node (ref "LD6") (pin "A") (pinfunction "A_A") (pintype "passive"))
      (node (ref "LD7") (pin "A") (pinfunction "A_A") (pintype "passive"))
      (node (ref "U$10") (pin "P13") (pinfunction "PWM2_P13") (pintype "bidirectional"))
    )
    (net (code "57") (name "Net-(U$10-PWM3)") (class "Default")
      (node (ref "LD8") (pin "A") (pinfunction "A_A") (pintype "passive"))
      (node (ref "LD9") (pin "A") (pinfunction "A_A") (pintype "passive"))
      (node (ref "U$10") (pin "P14") (pinfunction "PWM3_P14") (pintype "bidirectional"))
    )
    (net (code "58") (name "Net-(U$10-PWM4)") (class "Default")
      (node (ref "LD10") (pin "A") (pinfunction "A_A") (pintype "passive"))
      (node (ref "LD11") (pin "A") (pinfunction "A_A") (pintype "passive"))
      (node (ref "U$10") (pin "P15") (pinfunction "PWM4_P15") (pintype "bidirectional"))
    )
    (net (code "59") (name "Net-(U$10-PWM6)") (class "Default")
      (node (ref "LD12") (pin "A") (pinfunction "A_A") (pintype "passive"))
      (node (ref "LD13") (pin "A") (pinfunction "A_A") (pintype "passive"))
      (node (ref "U$10") (pin "P17") (pinfunction "PWM6_P17") (pintype "bidirectional"))
    )
    (net (code "60") (name "Net-(U$10-PWM7)") (class "Default")
      (node (ref "LD14") (pin "A") (pinfunction "A_A") (pintype "passive"))
      (node (ref "LD15") (pin "A") (pinfunction "A_A") (pintype "passive"))
      (node (ref "U$10") (pin "P18") (pinfunction "PWM7_P18") (pintype "bidirectional"))
    )
    (net (code "61") (name "Net-(U$10-PWM8)") (class "Default")
      (node (ref "LD16") (pin "A") (pinfunction "A_A") (pintype "passive"))
      (node (ref "LD17") (pin "A") (pinfunction "A_A") (pintype "passive"))
      (node (ref "U$10") (pin "P19") (pinfunction "PWM8_P19") (pintype "bidirectional"))
    )
    (net (code "62") (name "Net-(U$10-PWM9)") (class "Default")
      (node (ref "LD18") (pin "A") (pinfunction "A_A") (pintype "passive"))
      (node (ref "LD19") (pin "A") (pinfunction "A_A") (pintype "passive"))
      (node (ref "U$10") (pin "P20") (pinfunction "PWM9_P20") (pintype "bidirectional"))
    )
    (net (code "63") (name "Net-(U$10-PWM10)") (class "Default")
      (node (ref "LD20") (pin "A") (pinfunction "A_A") (pintype "passive"))
      (node (ref "LD21") (pin "A") (pinfunction "A_A") (pintype "passive"))
      (node (ref "U$10") (pin "P21") (pinfunction "PWM10_P21") (pintype "bidirectional"))
    )
    (net (code "64") (name "Net-(U$10-PWM11)") (class "Default")
      (node (ref "LD22") (pin "A") (pinfunction "A_A") (pintype "passive"))
      (node (ref "LD23") (pin "A") (pinfunction "A_A") (pintype "passive"))
      (node (ref "U$10") (pin "P22") (pinfunction "PWM11_P22") (pintype "bidirectional"))
    )
    (net (code "65") (name "Net-(U$10-PWM12)") (class "Default")
      (node (ref "LD24") (pin "A") (pinfunction "A_A") (pintype "passive"))
      (node (ref "LD25") (pin "A") (pinfunction "A_A") (pintype "passive"))
      (node (ref "U$10") (pin "P23") (pinfunction "PWM12_P23") (pintype "bidirectional"))
    )
    (net (code "66") (name "Net-(U$10-PWM13)") (class "Default")
      (node (ref "LD26") (pin "A") (pinfunction "A_A") (pintype "passive"))
      (node (ref "LD27") (pin "A") (pinfunction "A_A") (pintype "passive"))
      (node (ref "U$10") (pin "P24") (pinfunction "PWM13_P24") (pintype "bidirectional"))
    )
    (net (code "67") (name "Net-(U$10-PWM14)") (class "Default")
      (node (ref "LD28") (pin "A") (pinfunction "A_A") (pintype "passive"))
      (node (ref "LD29") (pin "A") (pinfunction "A_A") (pintype "passive"))
      (node (ref "U$10") (pin "P25") (pinfunction "PWM14_P25") (pintype "bidirectional"))
    )
    (net (code "68") (name "Net-(U$10-PWM15)") (class "Default")
      (node (ref "LD30") (pin "A") (pinfunction "A_A") (pintype "passive"))
      (node (ref "LD31") (pin "A") (pinfunction "A_A") (pintype "passive"))
      (node (ref "U$10") (pin "P26") (pinfunction "PWM15_P26") (pintype "bidirectional"))
    )
    (net (code "69") (name "Net-(U$10-SCL2)") (class "Default")
      (node (ref "U$10") (pin "P3") (pinfunction "SCL2_P3") (pintype "bidirectional"))
      (node (ref "U$9") (pin "PSOC23") (pinfunction "P4.0_PSOC23") (pintype "bidirectional"))
    )
    (net (code "70") (name "Net-(U$10-SDA1)") (class "Default")
      (node (ref "U$10") (pin "P4") (pinfunction "SDA1_P4") (pintype "bidirectional"))
      (node (ref "U$9") (pin "PSOC24") (pinfunction "P4.1_PSOC24") (pintype "bidirectional"))
    )
    (net (code "71") (name "unconnected-(DIS1-SUB1-Pad7)") (class "Default")
      (node (ref "DIS1") (pin "7") (pinfunction "SUB1_7") (pintype "passive"))
    )
    (net (code "72") (name "unconnected-(DIS1-SUB2-Pad8)") (class "Default")
      (node (ref "DIS1") (pin "8") (pinfunction "SUB2_8") (pintype "passive"))
    )
    (net (code "73") (name "unconnected-(DIS1-SUB3-Pad9)") (class "Default")
      (node (ref "DIS1") (pin "9") (pinfunction "SUB3_9") (pintype "passive"))
    )
    (net (code "74") (name "unconnected-(DIS2-SUB1-Pad7)") (class "Default")
      (node (ref "DIS2") (pin "7") (pinfunction "SUB1_7") (pintype "passive"))
    )
    (net (code "75") (name "unconnected-(DIS2-SUB2-Pad8)") (class "Default")
      (node (ref "DIS2") (pin "8") (pinfunction "SUB2_8") (pintype "passive"))
    )
    (net (code "76") (name "unconnected-(DIS2-SUB3-Pad9)") (class "Default")
      (node (ref "DIS2") (pin "9") (pinfunction "SUB3_9") (pintype "passive"))
    )
    (net (code "77") (name "unconnected-(DIS3-SUB1-Pad7)") (class "Default")
      (node (ref "DIS3") (pin "7") (pinfunction "SUB1_7") (pintype "passive"))
    )
    (net (code "78") (name "unconnected-(DIS3-SUB2-Pad8)") (class "Default")
      (node (ref "DIS3") (pin "8") (pinfunction "SUB2_8") (pintype "passive"))
    )
    (net (code "79") (name "unconnected-(DIS3-SUB3-Pad9)") (class "Default")
      (node (ref "DIS3") (pin "9") (pinfunction "SUB3_9") (pintype "passive"))
    )
    (net (code "80") (name "unconnected-(JP2-Pad3)") (class "Default")
      (node (ref "JP2") (pin "3") (pinfunction "3_3") (pintype "passive"))
    )
    (net (code "81") (name "unconnected-(U$9-P0.4-PadPSOC31)") (class "Default")
      (node (ref "U$9") (pin "PSOC31") (pinfunction "P0.4_PSOC31") (pintype "bidirectional"))
    )
    (net (code "82") (name "unconnected-(U$9-P0.5-PadPSOC32)") (class "Default")
      (node (ref "U$9") (pin "PSOC32") (pinfunction "P0.5_PSOC32") (pintype "bidirectional"))
    )
    (net (code "83") (name "unconnected-(U$9-RESET-PadPSOC20)") (class "Default")
      (node (ref "U$9") (pin "PSOC20") (pinfunction "RESET_PSOC20") (pintype "bidirectional"))
    )
    (net (code "84") (name "unconnected-(U$9-SWDCLK-PadPSOC19)") (class "Default")
      (node (ref "U$9") (pin "PSOC19") (pinfunction "SWDCLK_PSOC19") (pintype "bidirectional"))
    )
    (net (code "85") (name "unconnected-(U$9-SWDIO-PadPSOC18)") (class "Default")
      (node (ref "U$9") (pin "PSOC18") (pinfunction "SWDIO_PSOC18") (pintype "bidirectional"))
    )
    (net (code "86") (name "unconnected-(U$10-OE1-PadP7)") (class "Default")
      (node (ref "U$10") (pin "P7") (pinfunction "OE1_P7") (pintype "bidirectional"))
    )
    (net (code "87") (name "unconnected-(U$10-PWM5-PadP16)") (class "Default")
      (node (ref "U$10") (pin "P16") (pinfunction "PWM5_P16") (pintype "bidirectional"))
    )
    (net (code "88") (name "unconnected-(U$10-SCL1-PadP8)") (class "Default")
      (node (ref "U$10") (pin "P8") (pinfunction "SCL1_P8") (pintype "bidirectional"))
    )
    (net (code "89") (name "unconnected-(U$10-SDA2-PadP9)") (class "Default")
      (node (ref "U$10") (pin "P9") (pinfunction "SDA2_P9") (pintype "bidirectional"))
    )
  )
)
